# hhv-dcdarknet.net
KiCad netlist of a schematic drawn in EAGLE
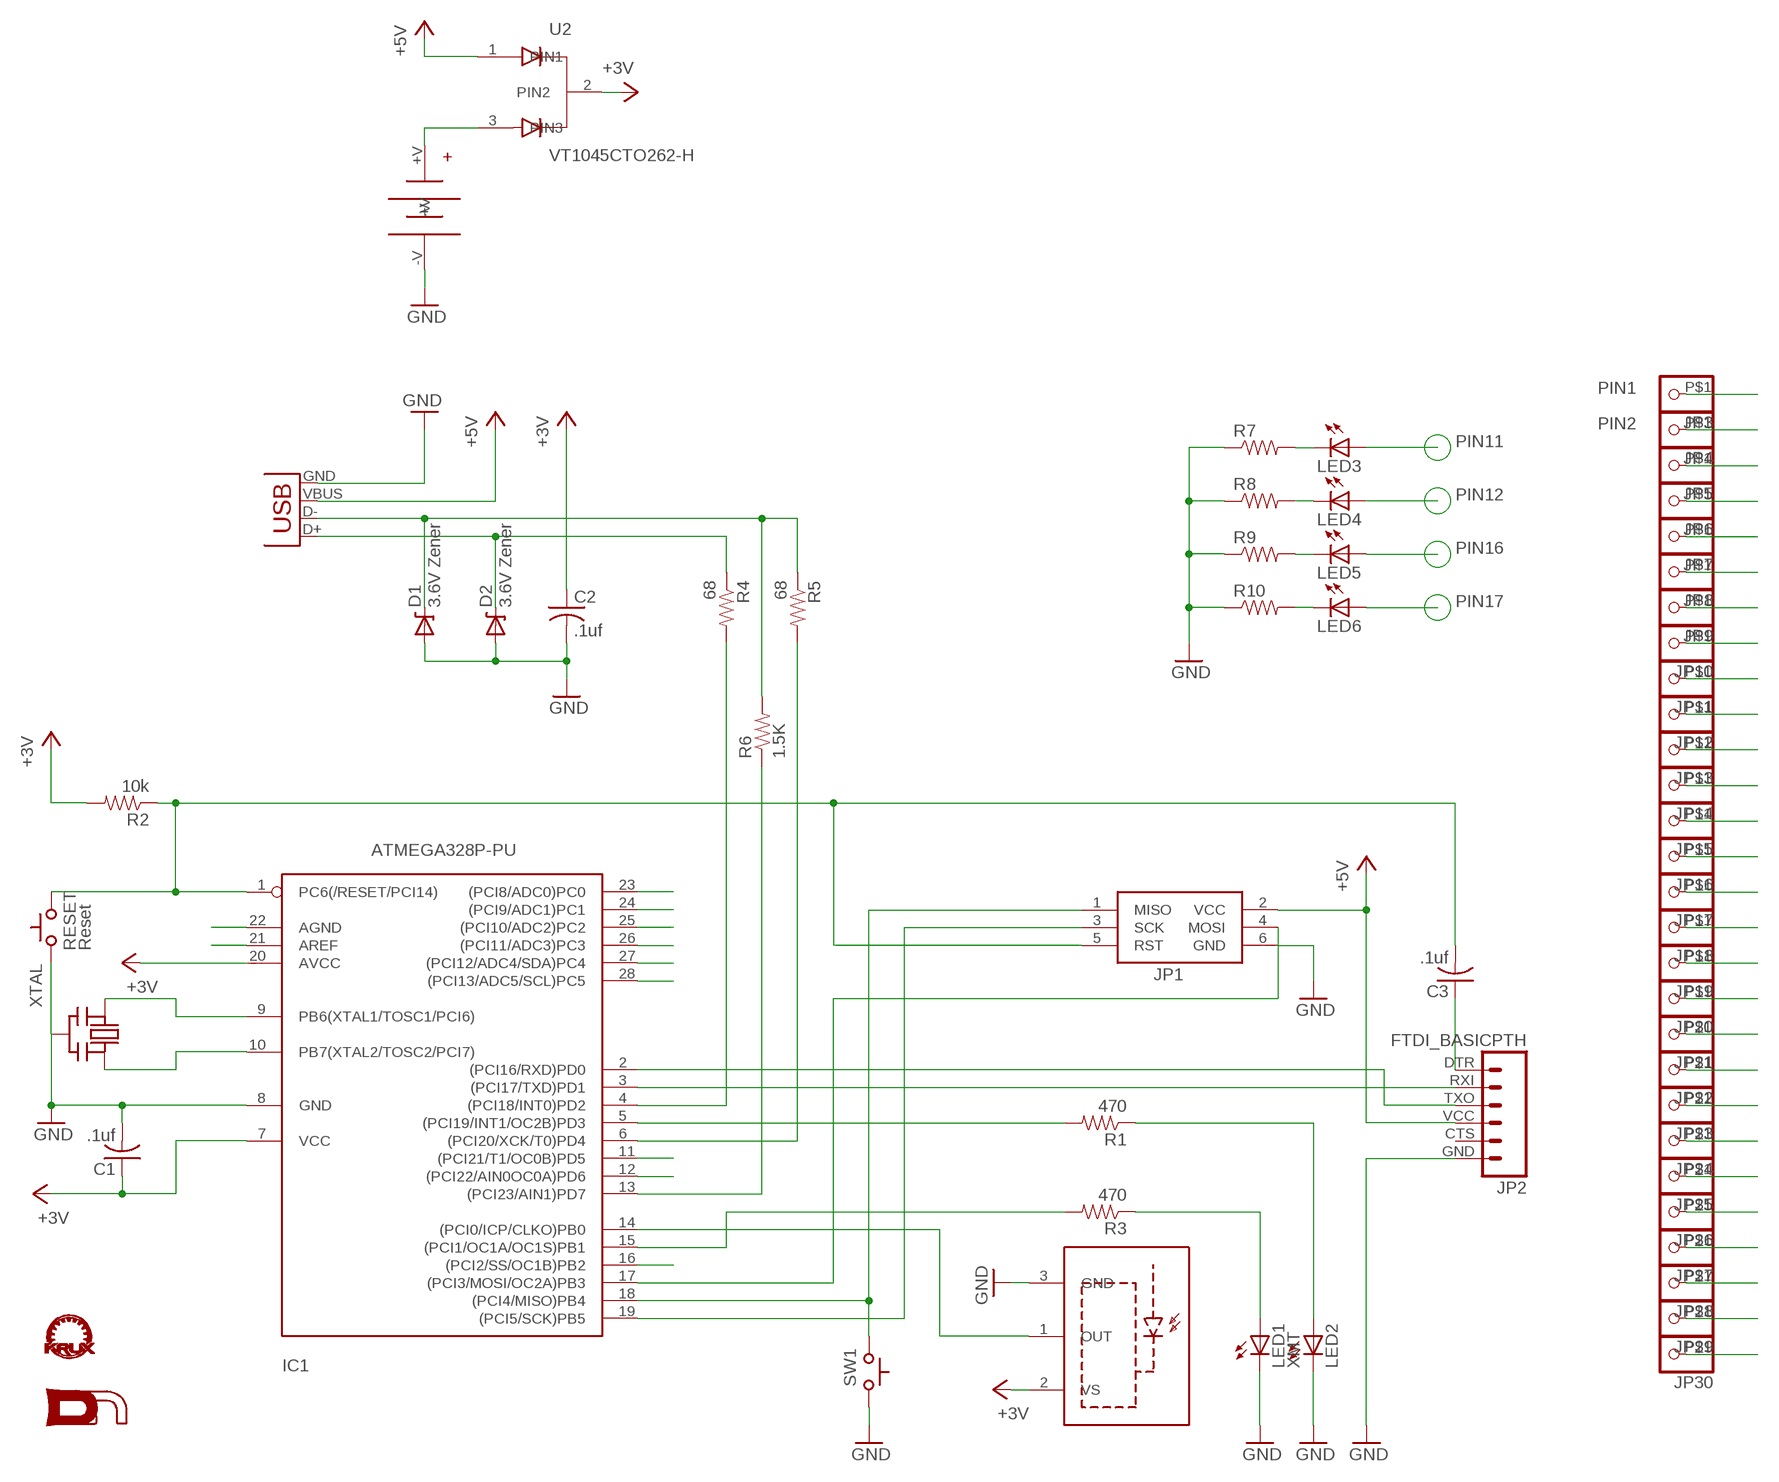
[diagram p0: schematic, sheet 1]

(export (version "E")
  (design (tool "Eeschema 10.0.6"))
  (components
    (comp (ref "C1")
      (value ".1uf")
      (footprint "eagle-import:C025-030X050")
      (libsource (lib "eagle-import") (part "C-US025-030X050"))
    )
    (comp (ref "C2")
      (value ".1uf")
      (footprint "eagle-import:C025-030X050")
      (libsource (lib "eagle-import") (part "C-US025-030X050"))
    )
    (comp (ref "C3")
      (value ".1uf")
      (footprint "eagle-import:C025-030X050")
      (libsource (lib "eagle-import") (part "C-US025-030X050"))
    )
    (comp (ref "D1")
      (value "3.6V Zener")
      (footprint "eagle-import:DIODE-ZENER")
      (libsource (lib "eagle-import") (part "DIODE-ZENERPTH"))
    )
    (comp (ref "D2")
      (value "3.6V Zener")
      (footprint "eagle-import:DIODE-ZENER")
      (libsource (lib "eagle-import") (part "DIODE-ZENERPTH"))
    )
    (comp (ref "IC1")
      (value "ATMEGA328P-PU")
      (footprint "eagle-import:DIL28-3")
      (libsource (lib "eagle-import") (part "ATMEGA168PV-10"))
    )
    (comp (ref "JP1")
      (value "JP1")
      (footprint "eagle-import:AVRISP")
      (libsource (lib "eagle-import") (part "AVRISP-6"))
    )
    (comp (ref "JP2")
      (value "FTDI_BASICPTH")
      (footprint "eagle-import:FTDI_BASIC")
      (libsource (lib "eagle-import") (part "FTDI_BASICPTH"))
    )
    (comp (ref "JP3")
      (value "PINHD-1X11X1_SQUARE")
      (footprint "eagle-import:1X1-SMALL_CUT")
      (libsource (lib "eagle-import") (part "PINHD-1X11X1_SQUARE"))
    )
    (comp (ref "JP4")
      (value "PINHD-1X11X1_SQUARE")
      (footprint "eagle-import:1X1-SMALL_CUT")
      (libsource (lib "eagle-import") (part "PINHD-1X11X1_SQUARE"))
    )
    (comp (ref "JP5")
      (value "PINHD-1X11X1_SQUARE")
      (footprint "eagle-import:1X1-SMALL_CUT")
      (libsource (lib "eagle-import") (part "PINHD-1X11X1_SQUARE"))
    )
    (comp (ref "JP6")
      (value "PINHD-1X11X1_SQUARE")
      (footprint "eagle-import:1X1-SMALL_CUT")
      (libsource (lib "eagle-import") (part "PINHD-1X11X1_SQUARE"))
    )
    (comp (ref "JP7")
      (value "PINHD-1X11X1_SQUARE")
      (footprint "eagle-import:1X1-SMALL_CUT")
      (libsource (lib "eagle-import") (part "PINHD-1X11X1_SQUARE"))
    )
    (comp (ref "JP8")
      (value "PINHD-1X11X1_SQUARE")
      (footprint "eagle-import:1X1-SMALL_CUT")
      (libsource (lib "eagle-import") (part "PINHD-1X11X1_SQUARE"))
    )
    (comp (ref "JP9")
      (value "PINHD-1X11X1_SQUARE")
      (footprint "eagle-import:1X1-SMALL_CUT")
      (libsource (lib "eagle-import") (part "PINHD-1X11X1_SQUARE"))
    )
    (comp (ref "JP10")
      (value "PINHD-1X11X1_SQUARE")
      (footprint "eagle-import:1X1-SMALL_CUT")
      (libsource (lib "eagle-import") (part "PINHD-1X11X1_SQUARE"))
    )
    (comp (ref "JP11")
      (value "PINHD-1X11X1_SQUARE")
      (footprint "eagle-import:1X1-SMALL_CUT")
      (libsource (lib "eagle-import") (part "PINHD-1X11X1_SQUARE"))
    )
    (comp (ref "JP12")
      (value "PINHD-1X11X1_SQUARE")
      (footprint "eagle-import:1X1-SMALL_CUT")
      (libsource (lib "eagle-import") (part "PINHD-1X11X1_SQUARE"))
    )
    (comp (ref "JP13")
      (value "PINHD-1X11X1_SQUARE")
      (footprint "eagle-import:1X1-SMALL_CUT")
      (libsource (lib "eagle-import") (part "PINHD-1X11X1_SQUARE"))
    )
    (comp (ref "JP14")
      (value "PINHD-1X11X1_SQUARE")
      (footprint "eagle-import:1X1-SMALL_CUT")
      (libsource (lib "eagle-import") (part "PINHD-1X11X1_SQUARE"))
    )
    (comp (ref "JP15")
      (value "PINHD-1X11X1_SQUARE")
      (footprint "eagle-import:1X1-SMALL_CUT")
      (libsource (lib "eagle-import") (part "PINHD-1X11X1_SQUARE"))
    )
    (comp (ref "JP16")
      (value "PINHD-1X11X1_SQUARE")
      (footprint "eagle-import:1X1-SMALL_CUT")
      (libsource (lib "eagle-import") (part "PINHD-1X11X1_SQUARE"))
    )
    (comp (ref "JP17")
      (value "PINHD-1X11X1_SQUARE")
      (footprint "eagle-import:1X1-SMALL_CUT")
      (libsource (lib "eagle-import") (part "PINHD-1X11X1_SQUARE"))
    )
    (comp (ref "JP18")
      (value "PINHD-1X11X1_SQUARE")
      (footprint "eagle-import:1X1-SMALL_CUT")
      (libsource (lib "eagle-import") (part "PINHD-1X11X1_SQUARE"))
    )
    (comp (ref "JP19")
      (value "PINHD-1X11X1_SQUARE")
      (footprint "eagle-import:1X1-SMALL_CUT")
      (libsource (lib "eagle-import") (part "PINHD-1X11X1_SQUARE"))
    )
    (comp (ref "JP20")
      (value "PINHD-1X11X1_SQUARE")
      (footprint "eagle-import:1X1-SMALL_CUT")
      (libsource (lib "eagle-import") (part "PINHD-1X11X1_SQUARE"))
    )
    (comp (ref "JP21")
      (value "PINHD-1X11X1_SQUARE")
      (footprint "eagle-import:1X1-SMALL_CUT")
      (libsource (lib "eagle-import") (part "PINHD-1X11X1_SQUARE"))
    )
    (comp (ref "JP22")
      (value "PINHD-1X11X1_SQUARE")
      (footprint "eagle-import:1X1-SMALL_CUT")
      (libsource (lib "eagle-import") (part "PINHD-1X11X1_SQUARE"))
    )
    (comp (ref "JP23")
      (value "PINHD-1X11X1_SQUARE")
      (footprint "eagle-import:1X1-SMALL_CUT")
      (libsource (lib "eagle-import") (part "PINHD-1X11X1_SQUARE"))
    )
    (comp (ref "JP24")
      (value "PINHD-1X11X1_SQUARE")
      (footprint "eagle-import:1X1-SMALL_CUT")
      (libsource (lib "eagle-import") (part "PINHD-1X11X1_SQUARE"))
    )
    (comp (ref "JP25")
      (value "PINHD-1X11X1_SQUARE")
      (footprint "eagle-import:1X1-SMALL_CUT")
      (libsource (lib "eagle-import") (part "PINHD-1X11X1_SQUARE"))
    )
    (comp (ref "JP26")
      (value "PINHD-1X11X1_SQUARE")
      (footprint "eagle-import:1X1-SMALL_CUT")
      (libsource (lib "eagle-import") (part "PINHD-1X11X1_SQUARE"))
    )
    (comp (ref "JP27")
      (value "PINHD-1X11X1_SQUARE")
      (footprint "eagle-import:1X1-SMALL_CUT")
      (libsource (lib "eagle-import") (part "PINHD-1X11X1_SQUARE"))
    )
    (comp (ref "JP28")
      (value "PINHD-1X11X1_SQUARE")
      (footprint "eagle-import:1X1-SMALL_CUT")
      (libsource (lib "eagle-import") (part "PINHD-1X11X1_SQUARE"))
    )
    (comp (ref "JP29")
      (value "PINHD-1X11X1_SQUARE")
      (footprint "eagle-import:1X1-SMALL_CUT")
      (libsource (lib "eagle-import") (part "PINHD-1X11X1_SQUARE"))
    )
    (comp (ref "JP30")
      (value "PINHD-1X11X1_SQUARE")
      (footprint "eagle-import:1X1-SMALL_CUT")
      (libsource (lib "eagle-import") (part "PINHD-1X11X1_SQUARE"))
    )
    (comp (ref "LED1")
      (value "XMT")
      (footprint "eagle-import:LED5MM")
      (libsource (lib "eagle-import") (part "LED5MM"))
    )
    (comp (ref "LED2")
      (value "LED5MM")
      (footprint "eagle-import:LED5MM")
      (libsource (lib "eagle-import") (part "LED5MM"))
    )
    (comp (ref "LED3")
      (value "LED1206")
      (footprint "eagle-import:LED-1206")
      (libsource (lib "eagle-import") (part "SparkFun_LED1206"))
    )
    (comp (ref "LED4")
      (value "LED1206")
      (footprint "eagle-import:LED-1206")
      (libsource (lib "eagle-import") (part "SparkFun_LED1206"))
    )
    (comp (ref "LED5")
      (value "LED1206")
      (footprint "eagle-import:LED-1206")
      (libsource (lib "eagle-import") (part "SparkFun_LED1206"))
    )
    (comp (ref "LED6")
      (value "LED1206")
      (footprint "eagle-import:LED-1206")
      (libsource (lib "eagle-import") (part "SparkFun_LED1206"))
    )
    (comp (ref "R1")
      (value "470")
      (footprint "eagle-import:AXIAL-0.3")
      (libsource (lib "eagle-import") (part "RESISTORAXIAL-0.3"))
    )
    (comp (ref "R2")
      (value "10k")
      (footprint "eagle-import:AXIAL-0.3")
      (libsource (lib "eagle-import") (part "RESISTORAXIAL-0.3"))
    )
    (comp (ref "R3")
      (value "470")
      (footprint "eagle-import:AXIAL-0.3")
      (libsource (lib "eagle-import") (part "RESISTORAXIAL-0.3"))
    )
    (comp (ref "R4")
      (value "68")
      (footprint "eagle-import:AXIAL-0.3")
      (libsource (lib "eagle-import") (part "RESISTORAXIAL-0.3"))
    )
    (comp (ref "R5")
      (value "68")
      (footprint "eagle-import:AXIAL-0.3")
      (libsource (lib "eagle-import") (part "RESISTORAXIAL-0.3"))
    )
    (comp (ref "R6")
      (value "1.5K")
      (footprint "eagle-import:AXIAL-0.3")
      (libsource (lib "eagle-import") (part "RESISTORAXIAL-0.3"))
    )
    (comp (ref "R7")
      (value "RESISTOR1206")
      (footprint "eagle-import:1206")
      (libsource (lib "eagle-import") (part "SparkFun_RESISTOR1206"))
    )
    (comp (ref "R8")
      (value "RESISTOR1206")
      (footprint "eagle-import:1206")
      (libsource (lib "eagle-import") (part "SparkFun_RESISTOR1206"))
    )
    (comp (ref "R9")
      (value "RESISTOR1206")
      (footprint "eagle-import:1206")
      (libsource (lib "eagle-import") (part "SparkFun_RESISTOR1206"))
    )
    (comp (ref "R10")
      (value "RESISTOR1206")
      (footprint "eagle-import:1206")
      (libsource (lib "eagle-import") (part "SparkFun_RESISTOR1206"))
    )
    (comp (ref "RESET")
      (value "Reset")
      (footprint "eagle-import:TACTILE-2PIN")
      (libsource (lib "eagle-import") (part "SWITCH_TACTILETACTILE-2PIN"))
    )
    (comp (ref "SW1")
      (value "SWITCH_TACTILETACTILE-2PIN")
      (footprint "eagle-import:TACTILE-2PIN")
      (libsource (lib "eagle-import") (part "SWITCH_TACTILETACTILE-2PIN"))
    )
    (comp (ref "U$1")
      (value "DN_LOGO")
      (footprint "eagle-import:DN_LOGO")
      (libsource (lib "eagle-import") (part "DN_LOGO"))
    )
    (comp (ref "U$5")
      (value "12BH423-GR3-CELL_NOBORDER")
      (footprint "eagle-import:3-AAA-CELL_NOBORDER")
      (libsource (lib "eagle-import") (part "12BH423-GR3-CELL_NOBORDER"))
    )
    (comp (ref "U$7")
      (value "KRUX_LOGO")
      (footprint "eagle-import:KRUX_LOGO")
      (libsource (lib "eagle-import") (part "KRUX_LOGO"))
    )
    (comp (ref "U1")
      (value "RCV")
      (footprint "eagle-import:IR-MODULE")
      (libsource (lib "eagle-import") (part "SOP22"))
    )
    (comp (ref "U2")
      (value "VT1045CTO262-H")
      (footprint "eagle-import:TO262-H")
      (libsource (lib "eagle-import") (part "VT1045CTO262-H"))
    )
    (comp (ref "X2")
      (value "USB")
      (footprint "eagle-import:USB-B-PTH")
      (libsource (lib "eagle-import") (part "USBPTH"))
    )
    (comp (ref "XTAL")
      (value "CERMOSCILL-THM")
      (footprint "eagle-import:CERM_OSC")
      (libsource (lib "eagle-import") (part "CERMOSCILL-THM"))
    )
  )
  (nets
    (net (code "1") (name "+3V") (class "Default")
      (node (ref "C1") (pin "1") (pinfunction "1_1") (pintype "passive"))
      (node (ref "C2") (pin "1") (pinfunction "1_1") (pintype "passive"))
      (node (ref "IC1") (pin "20") (pinfunction "AVCC_20") (pintype "bidirectional"))
      (node (ref "IC1") (pin "7") (pinfunction "VCC_7") (pintype "bidirectional"))
      (node (ref "JP22") (pin "P$1") (pinfunction "1_P$1") (pintype "passive"))
      (node (ref "JP9") (pin "P$1") (pinfunction "1_P$1") (pintype "passive"))
      (node (ref "R2") (pin "P$2") (pinfunction "2_P$2") (pintype "passive"))
      (node (ref "U1") (pin "2") (pinfunction "VS_2") (pintype "bidirectional"))
      (node (ref "U2") (pin "2") (pinfunction "PIN2_2") (pintype "bidirectional"))
    )
    (net (code "2") (name "+5V") (class "Default")
      (node (ref "JP1") (pin "2") (pinfunction "VCC_2") (pintype "power_in"))
      (node (ref "JP2") (pin "VCC") (pinfunction "4_VCC") (pintype "passive"))
      (node (ref "U2") (pin "1") (pinfunction "PIN1_1") (pintype "bidirectional"))
      (node (ref "X2") (pin "VBUS") (pinfunction "VBUS_VBUS") (pintype "bidirectional"))
    )
    (net (code "3") (name "/PIN1") (class "Default")
      (node (ref "C3") (pin "2") (pinfunction "2_2") (pintype "passive"))
      (node (ref "IC1") (pin "1") (pinfunction "PC6(/RESET/PCI14)_1") (pintype "bidirectional"))
      (node (ref "JP1") (pin "5") (pinfunction "RST_5") (pintype "output"))
      (node (ref "JP3") (pin "P$1") (pinfunction "1_P$1") (pintype "passive"))
      (node (ref "R2") (pin "P$1") (pinfunction "1_P$1") (pintype "passive"))
      (node (ref "RESET") (pin "P$1") (pinfunction "A_P$1") (pintype "passive"))
    )
    (net (code "4") (name "/PIN2") (class "Default")
      (node (ref "IC1") (pin "2") (pinfunction "(PCI16/RXD)PD0_2") (pintype "bidirectional"))
      (node (ref "JP2") (pin "TXO") (pinfunction "3_TXO") (pintype "passive"))
      (node (ref "JP4") (pin "P$1") (pinfunction "1_P$1") (pintype "passive"))
    )
    (net (code "5") (name "/PIN3") (class "Default")
      (node (ref "IC1") (pin "3") (pinfunction "(PCI17/TXD)PD1_3") (pintype "bidirectional"))
      (node (ref "JP2") (pin "RXI") (pinfunction "2_RXI") (pintype "passive"))
      (node (ref "JP5") (pin "P$1") (pinfunction "1_P$1") (pintype "passive"))
    )
    (net (code "6") (name "/PIN4") (class "Default")
      (node (ref "IC1") (pin "4") (pinfunction "(PCI18/INT0)PD2_4") (pintype "bidirectional"))
      (node (ref "JP6") (pin "P$1") (pinfunction "1_P$1") (pintype "passive"))
      (node (ref "R4") (pin "P$2") (pinfunction "2_P$2") (pintype "passive"))
    )
    (net (code "7") (name "/PIN5") (class "Default")
      (node (ref "IC1") (pin "5") (pinfunction "(PCI19/INT1/OC2B)PD3_5") (pintype "bidirectional"))
      (node (ref "JP7") (pin "P$1") (pinfunction "1_P$1") (pintype "passive"))
      (node (ref "R1") (pin "P$2") (pinfunction "2_P$2") (pintype "passive"))
    )
    (net (code "8") (name "/PIN6") (class "Default")
      (node (ref "IC1") (pin "6") (pinfunction "(PCI20/XCK/T0)PD4_6") (pintype "bidirectional"))
      (node (ref "JP8") (pin "P$1") (pinfunction "1_P$1") (pintype "passive"))
      (node (ref "R5") (pin "P$2") (pinfunction "2_P$2") (pintype "passive"))
    )
    (net (code "9") (name "/PIN9") (class "Default")
      (node (ref "IC1") (pin "9") (pinfunction "PB6(XTAL1/TOSC1/PCI6)_9") (pintype "bidirectional"))
      (node (ref "JP11") (pin "P$1") (pinfunction "1_P$1") (pintype "passive"))
      (node (ref "XTAL") (pin "P$1") (pinfunction "IN_P$1") (pintype "bidirectional"))
    )
    (net (code "10") (name "/PIN10") (class "Default")
      (node (ref "IC1") (pin "10") (pinfunction "PB7(XTAL2/TOSC2/PCI7)_10") (pintype "bidirectional"))
      (node (ref "JP12") (pin "P$1") (pinfunction "1_P$1") (pintype "passive"))
      (node (ref "XTAL") (pin "P$3") (pinfunction "OUT_P$3") (pintype "bidirectional"))
    )
    (net (code "11") (name "/PIN11") (class "Default")
      (node (ref "IC1") (pin "11") (pinfunction "(PCI21/T1/OC0B)PD5_11") (pintype "bidirectional"))
      (node (ref "JP13") (pin "P$1") (pinfunction "1_P$1") (pintype "passive"))
      (node (ref "LED3") (pin "A") (pinfunction "A_A") (pintype "passive"))
    )
    (net (code "12") (name "/PIN12") (class "Default")
      (node (ref "IC1") (pin "12") (pinfunction "(PCI22/AIN0OC0A)PD6_12") (pintype "bidirectional"))
      (node (ref "JP14") (pin "P$1") (pinfunction "1_P$1") (pintype "passive"))
      (node (ref "LED4") (pin "A") (pinfunction "A_A") (pintype "passive"))
    )
    (net (code "13") (name "/PIN13") (class "Default")
      (node (ref "IC1") (pin "13") (pinfunction "(PCI23/AIN1)PD7_13") (pintype "bidirectional"))
      (node (ref "JP15") (pin "P$1") (pinfunction "1_P$1") (pintype "passive"))
      (node (ref "R6") (pin "P$1") (pinfunction "1_P$1") (pintype "passive"))
    )
    (net (code "14") (name "/PIN14") (class "Default")
      (node (ref "IC1") (pin "14") (pinfunction "(PCI0/ICP/CLKO)PB0_14") (pintype "bidirectional"))
      (node (ref "JP16") (pin "P$1") (pinfunction "1_P$1") (pintype "passive"))
      (node (ref "U1") (pin "1") (pinfunction "OUT_1") (pintype "bidirectional"))
    )
    (net (code "15") (name "/PIN15") (class "Default")
      (node (ref "IC1") (pin "15") (pinfunction "(PCI1/OC1A/OC1S)PB1_15") (pintype "bidirectional"))
      (node (ref "JP17") (pin "P$1") (pinfunction "1_P$1") (pintype "passive"))
      (node (ref "R3") (pin "P$2") (pinfunction "2_P$2") (pintype "passive"))
    )
    (net (code "16") (name "/PIN16") (class "Default")
      (node (ref "IC1") (pin "16") (pinfunction "(PCI2/SS/OC1B)PB2_16") (pintype "bidirectional"))
      (node (ref "JP18") (pin "P$1") (pinfunction "1_P$1") (pintype "passive"))
      (node (ref "LED5") (pin "A") (pinfunction "A_A") (pintype "passive"))
    )
    (net (code "17") (name "/PIN17") (class "Default")
      (node (ref "IC1") (pin "17") (pinfunction "(PCI3/MOSI/OC2A)PB3_17") (pintype "bidirectional"))
      (node (ref "JP1") (pin "4") (pinfunction "MOSI_4") (pintype "output"))
      (node (ref "JP19") (pin "P$1") (pinfunction "1_P$1") (pintype "passive"))
      (node (ref "LED6") (pin "A") (pinfunction "A_A") (pintype "passive"))
    )
    (net (code "18") (name "/PIN18") (class "Default")
      (node (ref "IC1") (pin "18") (pinfunction "(PCI4/MISO)PB4_18") (pintype "bidirectional"))
      (node (ref "JP1") (pin "1") (pinfunction "MISO_1") (pintype "input"))
      (node (ref "JP20") (pin "P$1") (pinfunction "1_P$1") (pintype "passive"))
      (node (ref "SW1") (pin "P$2") (pinfunction "C_P$2") (pintype "passive"))
    )
    (net (code "19") (name "/PIN19") (class "Default")
      (node (ref "IC1") (pin "19") (pinfunction "(PCI5/SCK)PB5_19") (pintype "bidirectional"))
      (node (ref "JP1") (pin "3") (pinfunction "SCK_3") (pintype "output"))
      (node (ref "JP21") (pin "P$1") (pinfunction "1_P$1") (pintype "passive"))
    )
    (net (code "20") (name "/PIN21") (class "Default")
      (node (ref "IC1") (pin "21") (pinfunction "AREF_21") (pintype "bidirectional"))
      (node (ref "JP23") (pin "P$1") (pinfunction "1_P$1") (pintype "passive"))
    )
    (net (code "21") (name "/PIN22") (class "Default")
      (node (ref "IC1") (pin "22") (pinfunction "AGND_22") (pintype "bidirectional"))
      (node (ref "JP24") (pin "P$1") (pinfunction "1_P$1") (pintype "passive"))
    )
    (net (code "22") (name "/PIN23") (class "Default")
      (node (ref "IC1") (pin "23") (pinfunction "(PCI8/ADC0)PC0_23") (pintype "bidirectional"))
      (node (ref "JP25") (pin "P$1") (pinfunction "1_P$1") (pintype "passive"))
    )
    (net (code "23") (name "/PIN24") (class "Default")
      (node (ref "IC1") (pin "24") (pinfunction "(PCI9/ADC1)PC1_24") (pintype "bidirectional"))
      (node (ref "JP26") (pin "P$1") (pinfunction "1_P$1") (pintype "passive"))
    )
    (net (code "24") (name "/PIN25") (class "Default")
      (node (ref "IC1") (pin "25") (pinfunction "(PCI10/ADC2)PC2_25") (pintype "bidirectional"))
      (node (ref "JP27") (pin "P$1") (pinfunction "1_P$1") (pintype "passive"))
    )
    (net (code "25") (name "/PIN26") (class "Default")
      (node (ref "IC1") (pin "26") (pinfunction "(PCI11/ADC3)PC3_26") (pintype "bidirectional"))
      (node (ref "JP28") (pin "P$1") (pinfunction "1_P$1") (pintype "passive"))
    )
    (net (code "26") (name "/PIN27") (class "Default")
      (node (ref "IC1") (pin "27") (pinfunction "(PCI12/ADC4/SDA)PC4_27") (pintype "bidirectional"))
      (node (ref "JP29") (pin "P$1") (pinfunction "1_P$1") (pintype "passive"))
    )
    (net (code "27") (name "/PIN28") (class "Default")
      (node (ref "IC1") (pin "28") (pinfunction "(PCI13/ADC5/SCL)PC5_28") (pintype "bidirectional"))
      (node (ref "JP30") (pin "P$1") (pinfunction "1_P$1") (pintype "passive"))
    )
    (net (code "28") (name "GND") (class "Default")
      (node (ref "C1") (pin "2") (pinfunction "2_2") (pintype "passive"))
      (node (ref "C2") (pin "2") (pinfunction "2_2") (pintype "passive"))
      (node (ref "D1") (pin "P$2") (pinfunction "A_P$2") (pintype "passive"))
      (node (ref "D2") (pin "P$2") (pinfunction "A_P$2") (pintype "passive"))
      (node (ref "IC1") (pin "8") (pinfunction "GND_8") (pintype "bidirectional"))
      (node (ref "JP1") (pin "6") (pinfunction "GND_6") (pintype "power_in"))
      (node (ref "JP10") (pin "P$1") (pinfunction "1_P$1") (pintype "passive"))
      (node (ref "JP2") (pin "GND") (pinfunction "6_GND") (pintype "passive"))
      (node (ref "LED1") (pin "K") (pinfunction "C_K") (pintype "passive"))
      (node (ref "LED2") (pin "K") (pinfunction "C_K") (pintype "passive"))
      (node (ref "R10") (pin "1") (pinfunction "1_1") (pintype "passive"))
      (node (ref "R7") (pin "1") (pinfunction "1_1") (pintype "passive"))
      (node (ref "R8") (pin "1") (pinfunction "1_1") (pintype "passive"))
      (node (ref "R9") (pin "1") (pinfunction "1_1") (pintype "passive"))
      (node (ref "RESET") (pin "P$2") (pinfunction "C_P$2") (pintype "passive"))
      (node (ref "SW1") (pin "P$1") (pinfunction "A_P$1") (pintype "passive"))
      (node (ref "U$5") (pin "-V") (pinfunction "-V_-V") (pintype "bidirectional"))
      (node (ref "U1") (pin "3") (pinfunction "GND_3") (pintype "bidirectional"))
      (node (ref "X2") (pin "GND") (pinfunction "GND_GND") (pintype "bidirectional"))
      (node (ref "XTAL") (pin "P$2") (pinfunction "GND_P$2") (pintype "bidirectional"))
    )
    (net (code "29") (name "Net-(D1-C)") (class "Default")
      (node (ref "D1") (pin "P$1") (pinfunction "C_P$1") (pintype "passive"))
      (node (ref "R5") (pin "P$1") (pinfunction "1_P$1") (pintype "passive"))
      (node (ref "R6") (pin "P$2") (pinfunction "2_P$2") (pintype "passive"))
      (node (ref "X2") (pin "D-") (pinfunction "D-_D-") (pintype "bidirectional"))
    )
    (net (code "30") (name "Net-(D2-C)") (class "Default")
      (node (ref "D2") (pin "P$1") (pinfunction "C_P$1") (pintype "passive"))
      (node (ref "R4") (pin "P$1") (pinfunction "1_P$1") (pintype "passive"))
      (node (ref "X2") (pin "D+") (pinfunction "D+_D+") (pintype "bidirectional"))
    )
    (net (code "31") (name "Net-(JP2-1)") (class "Default")
      (node (ref "C3") (pin "1") (pinfunction "1_1") (pintype "passive"))
      (node (ref "JP2") (pin "DTR") (pinfunction "1_DTR") (pintype "passive"))
    )
    (net (code "32") (name "Net-(LED3-PadC)") (class "Default")
      (node (ref "LED3") (pin "C") (pinfunction "C_C") (pintype "passive"))
      (node (ref "R7") (pin "2") (pinfunction "2_2") (pintype "passive"))
    )
    (net (code "33") (name "Net-(LED4-PadC)") (class "Default")
      (node (ref "LED4") (pin "C") (pinfunction "C_C") (pintype "passive"))
      (node (ref "R8") (pin "2") (pinfunction "2_2") (pintype "passive"))
    )
    (net (code "34") (name "Net-(LED5-PadC)") (class "Default")
      (node (ref "LED5") (pin "C") (pinfunction "C_C") (pintype "passive"))
      (node (ref "R9") (pin "2") (pinfunction "2_2") (pintype "passive"))
    )
    (net (code "35") (name "Net-(LED6-PadC)") (class "Default")
      (node (ref "LED6") (pin "C") (pinfunction "C_C") (pintype "passive"))
      (node (ref "R10") (pin "2") (pinfunction "2_2") (pintype "passive"))
    )
    (net (code "36") (name "Net-(R1-1)") (class "Default")
      (node (ref "LED2") (pin "A") (pinfunction "A_A") (pintype "passive"))
      (node (ref "R1") (pin "P$1") (pinfunction "1_P$1") (pintype "passive"))
    )
    (net (code "37") (name "Net-(R3-1)") (class "Default")
      (node (ref "LED1") (pin "A") (pinfunction "A_A") (pintype "passive"))
      (node (ref "R3") (pin "P$1") (pinfunction "1_P$1") (pintype "passive"))
    )
    (net (code "38") (name "Net-(U2-PIN3)") (class "Default")
      (node (ref "U$5") (pin "+V") (pinfunction "+V_+V") (pintype "bidirectional"))
      (node (ref "U2") (pin "3") (pinfunction "PIN3_3") (pintype "bidirectional"))
    )
    (net (code "39") (name "unconnected-(JP2-5-PadCTS)") (class "Default")
      (node (ref "JP2") (pin "CTS") (pinfunction "5_CTS") (pintype "passive"))
    )
  )
)
